# Nixie_3757.net
KiCad netlist of a schematic drawn in EAGLE
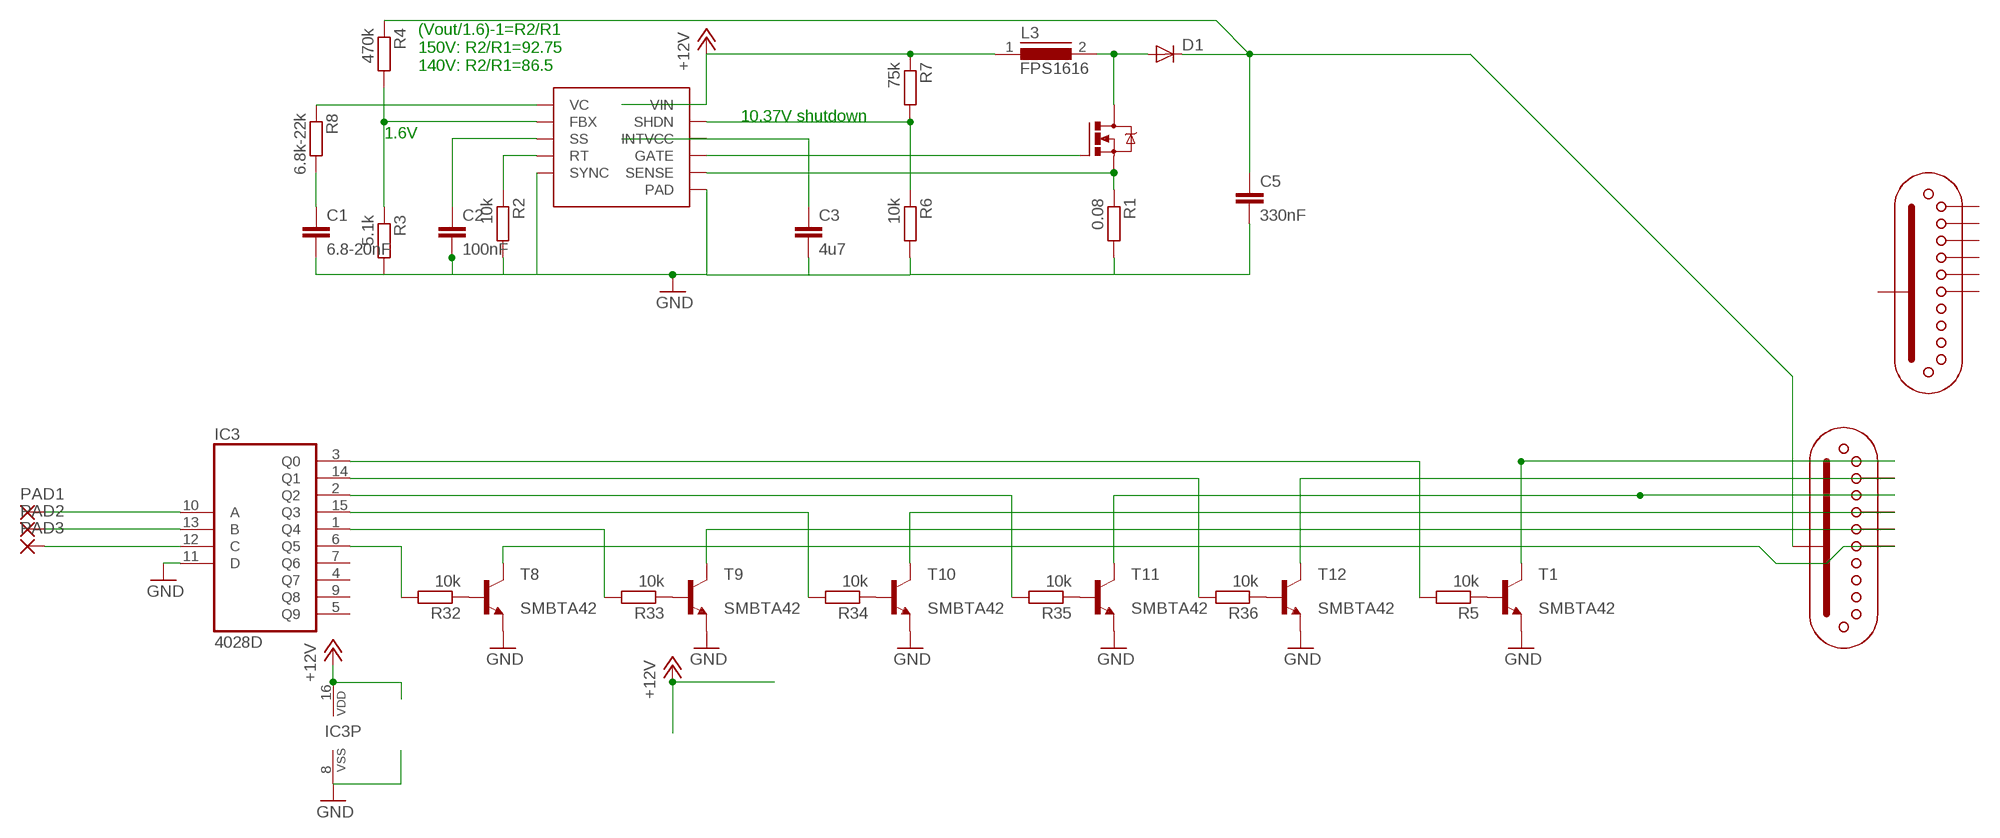
[diagram p0: schematic, sheet 1]

(export (version "E")
  (design (tool "Eeschema 10.0.6"))
  (components
    (comp (ref "C1")
      (value "6.8-20nF")
      (footprint "eagle-import:C0805K")
      (libsource (lib "eagle-import") (part "C-EUC0805K"))
    )
    (comp (ref "C2")
      (value "100nF")
      (footprint "eagle-import:C0805K")
      (libsource (lib "eagle-import") (part "C-EUC0805K"))
    )
    (comp (ref "C3")
      (value "4u7")
      (footprint "eagle-import:C0805K")
      (libsource (lib "eagle-import") (part "C-EUC0805K"))
    )
    (comp (ref "C5")
      (value "330nF")
      (footprint "eagle-import:C1812")
      (libsource (lib "eagle-import") (part "C-EUC1812"))
    )
    (comp (ref "D1")
      (value "DIODE-DO219AB")
      (footprint "eagle-import:DO219AB")
      (libsource (lib "eagle-import") (part "DIODE-DO219AB"))
    )
    (comp (ref "IC3")
      (value "4028D")
      (footprint "eagle-import:SO16")
      (libsource (lib "eagle-import") (part "4028D"))
    )
    (comp (ref "L3")
      (value "FPS1616")
      (footprint "eagle-import:1616FPS_22UH")
      (libsource (lib "eagle-import") (part "FPS1616"))
    )
    (comp (ref "PAD1")
      (value "1,6/0,8")
      (footprint "eagle-import:1,6_0,8")
      (libsource (lib "eagle-import") (part "1,6/0,8"))
    )
    (comp (ref "PAD2")
      (value "1,6/0,8")
      (footprint "eagle-import:1,6_0,8")
      (libsource (lib "eagle-import") (part "1,6/0,8"))
    )
    (comp (ref "PAD3")
      (value "1,6/0,8")
      (footprint "eagle-import:1,6_0,8")
      (libsource (lib "eagle-import") (part "1,6/0,8"))
    )
    (comp (ref "Q4")
      (value "N-MOSFET-TO252-DPAK")
      (footprint "eagle-import:TO252")
      (libsource (lib "eagle-import") (part "N-MOSFET-TO252-DPAK"))
    )
    (comp (ref "R1")
      (value "0.08")
      (footprint "eagle-import:R0805")
      (libsource (lib "eagle-import") (part "R-EU_R0805"))
    )
    (comp (ref "R2")
      (value "10k")
      (footprint "eagle-import:R0805")
      (libsource (lib "eagle-import") (part "R-EU_R0805"))
    )
    (comp (ref "R3")
      (value "5.1k")
      (footprint "eagle-import:R0805")
      (libsource (lib "eagle-import") (part "R-EU_R0805"))
    )
    (comp (ref "R4")
      (value "470k")
      (footprint "eagle-import:R0805")
      (libsource (lib "eagle-import") (part "R-EU_R0805"))
    )
    (comp (ref "R5")
      (value "10k")
      (footprint "eagle-import:R0805")
      (libsource (lib "eagle-import") (part "R-EU_R0805"))
    )
    (comp (ref "R6")
      (value "10k")
      (footprint "eagle-import:R0805")
      (libsource (lib "eagle-import") (part "R-EU_R0805"))
    )
    (comp (ref "R7")
      (value "75k")
      (footprint "eagle-import:R0805")
      (libsource (lib "eagle-import") (part "R-EU_R0805"))
    )
    (comp (ref "R8")
      (value "6.8k-22k")
      (footprint "eagle-import:R0805")
      (libsource (lib "eagle-import") (part "R-EU_R0805"))
    )
    (comp (ref "R32")
      (value "10k")
      (footprint "eagle-import:R0805")
      (libsource (lib "eagle-import") (part "R-EU_R0805"))
    )
    (comp (ref "R33")
      (value "10k")
      (footprint "eagle-import:R0805")
      (libsource (lib "eagle-import") (part "R-EU_R0805"))
    )
    (comp (ref "R34")
      (value "10k")
      (footprint "eagle-import:R0805")
      (libsource (lib "eagle-import") (part "R-EU_R0805"))
    )
    (comp (ref "R35")
      (value "10k")
      (footprint "eagle-import:R0805")
      (libsource (lib "eagle-import") (part "R-EU_R0805"))
    )
    (comp (ref "R36")
      (value "10k")
      (footprint "eagle-import:R0805")
      (libsource (lib "eagle-import") (part "R-EU_R0805"))
    )
    (comp (ref "T1")
      (value "MMBTA42LT1-NPN-SOT23-BEC")
      (footprint "eagle-import:SOT23-BEC")
      (fields (field (name "T") "SMBTA42"))
      (libsource (lib "eagle-import") (part "-NPN-SOT23-BECMMBTA42LT1"))
    )
    (comp (ref "T8")
      (value "MMBTA42LT1-NPN-SOT23-BEC")
      (footprint "eagle-import:SOT23-BEC")
      (fields (field (name "T") "SMBTA42"))
      (libsource (lib "eagle-import") (part "-NPN-SOT23-BECMMBTA42LT1"))
    )
    (comp (ref "T9")
      (value "MMBTA42LT1-NPN-SOT23-BEC")
      (footprint "eagle-import:SOT23-BEC")
      (fields (field (name "T") "SMBTA42"))
      (libsource (lib "eagle-import") (part "-NPN-SOT23-BECMMBTA42LT1"))
    )
    (comp (ref "T10")
      (value "MMBTA42LT1-NPN-SOT23-BEC")
      (footprint "eagle-import:SOT23-BEC")
      (fields (field (name "T") "SMBTA42"))
      (libsource (lib "eagle-import") (part "-NPN-SOT23-BECMMBTA42LT1"))
    )
    (comp (ref "T11")
      (value "MMBTA42LT1-NPN-SOT23-BEC")
      (footprint "eagle-import:SOT23-BEC")
      (fields (field (name "T") "SMBTA42"))
      (libsource (lib "eagle-import") (part "-NPN-SOT23-BECMMBTA42LT1"))
    )
    (comp (ref "T12")
      (value "MMBTA42LT1-NPN-SOT23-BEC")
      (footprint "eagle-import:SOT23-BEC")
      (fields (field (name "T") "SMBTA42"))
      (libsource (lib "eagle-import") (part "-NPN-SOT23-BECMMBTA42LT1"))
    )
    (comp (ref "U$1")
      (value "ZM1020")
      (footprint "eagle-import:ZM1020")
      (libsource (lib "eagle-import") (part "ZM1020"))
    )
    (comp (ref "U$3")
      (value "ZM1020")
      (footprint "eagle-import:ZM1020")
      (libsource (lib "eagle-import") (part "ZM1020"))
    )
    (comp (ref "U1")
      (value "LT3757MSOP-10")
      (footprint "eagle-import:MSOP-10")
      (libsource (lib "eagle-import") (part "LT3757MSOP-10"))
    )
  )
  (nets
    (net (code "1") (name "+12V") (class "Default")
      (node (ref "IC3") (pin "16") (pinfunction "VDD_16") (pintype "power_in"))
      (node (ref "L3") (pin "1") (pinfunction "1_1") (pintype "passive"))
      (node (ref "R7") (pin "1") (pinfunction "1_1") (pintype "passive"))
      (node (ref "U1") (pin "10") (pinfunction "VIN_10") (pintype "bidirectional"))
    )
    (net (code "2") (name "GND") (class "Default")
      (node (ref "C1") (pin "2") (pinfunction "2_2") (pintype "passive"))
      (node (ref "C2") (pin "2") (pinfunction "2_2") (pintype "passive"))
      (node (ref "C3") (pin "2") (pinfunction "2_2") (pintype "passive"))
      (node (ref "C5") (pin "2") (pinfunction "2_2") (pintype "passive"))
      (node (ref "IC3") (pin "11") (pinfunction "D_11") (pintype "input"))
      (node (ref "IC3") (pin "8") (pinfunction "VSS_8") (pintype "power_in"))
      (node (ref "R1") (pin "2") (pinfunction "2_2") (pintype "passive"))
      (node (ref "R2") (pin "2") (pinfunction "2_2") (pintype "passive"))
      (node (ref "R3") (pin "2") (pinfunction "2_2") (pintype "passive"))
      (node (ref "R6") (pin "2") (pinfunction "2_2") (pintype "passive"))
      (node (ref "T1") (pin "E") (pinfunction "E_E") (pintype "passive"))
      (node (ref "T10") (pin "E") (pinfunction "E_E") (pintype "passive"))
      (node (ref "T11") (pin "E") (pinfunction "E_E") (pintype "passive"))
      (node (ref "T12") (pin "E") (pinfunction "E_E") (pintype "passive"))
      (node (ref "T8") (pin "E") (pinfunction "E_E") (pintype "passive"))
      (node (ref "T9") (pin "E") (pinfunction "E_E") (pintype "passive"))
      (node (ref "U1") (pin "5") (pinfunction "SYNC_5") (pintype "bidirectional"))
      (node (ref "U1") (pin "PAD") (pinfunction "PAD_PAD") (pintype "bidirectional"))
    )
    (net (code "3") (name "Net-(C1-Pad1)") (class "Default")
      (node (ref "C1") (pin "1") (pinfunction "1_1") (pintype "passive"))
      (node (ref "R8") (pin "2") (pinfunction "2_2") (pintype "passive"))
    )
    (net (code "4") (name "Net-(IC3A-A)") (class "Default")
      (node (ref "IC3") (pin "10") (pinfunction "A_10") (pintype "input"))
      (node (ref "PAD1") (pin "1") (pinfunction "P_1") (pintype "passive"))
    )
    (net (code "5") (name "Net-(IC3A-B)") (class "Default")
      (node (ref "IC3") (pin "13") (pinfunction "B_13") (pintype "input"))
      (node (ref "PAD2") (pin "1") (pinfunction "P_1") (pintype "passive"))
    )
    (net (code "6") (name "Net-(IC3A-C)") (class "Default")
      (node (ref "IC3") (pin "12") (pinfunction "C_12") (pintype "input"))
      (node (ref "PAD3") (pin "1") (pinfunction "P_1") (pintype "passive"))
    )
    (net (code "7") (name "Net-(IC3A-Q0)") (class "Default")
      (node (ref "IC3") (pin "3") (pinfunction "Q0_3") (pintype "output"))
      (node (ref "R5") (pin "2") (pinfunction "2_2") (pintype "passive"))
    )
    (net (code "8") (name "Net-(IC3A-Q1)") (class "Default")
      (node (ref "IC3") (pin "14") (pinfunction "Q1_14") (pintype "output"))
      (node (ref "R36") (pin "2") (pinfunction "2_2") (pintype "passive"))
    )
    (net (code "9") (name "Net-(IC3A-Q2)") (class "Default")
      (node (ref "IC3") (pin "2") (pinfunction "Q2_2") (pintype "output"))
      (node (ref "R35") (pin "2") (pinfunction "2_2") (pintype "passive"))
    )
    (net (code "10") (name "Net-(IC3A-Q3)") (class "Default")
      (node (ref "IC3") (pin "15") (pinfunction "Q3_15") (pintype "output"))
      (node (ref "R34") (pin "2") (pinfunction "2_2") (pintype "passive"))
    )
    (net (code "11") (name "Net-(IC3A-Q4)") (class "Default")
      (node (ref "IC3") (pin "1") (pinfunction "Q4_1") (pintype "output"))
      (node (ref "R33") (pin "2") (pinfunction "2_2") (pintype "passive"))
    )
    (net (code "12") (name "Net-(IC3A-Q5)") (class "Default")
      (node (ref "IC3") (pin "6") (pinfunction "Q5_6") (pintype "output"))
      (node (ref "R32") (pin "2") (pinfunction "2_2") (pintype "passive"))
    )
    (net (code "13") (name "Net-(Q4-D)") (class "Default")
      (node (ref "D1") (pin "A") (pinfunction "A_A") (pintype "passive"))
      (node (ref "L3") (pin "2") (pinfunction "2_2") (pintype "passive"))
      (node (ref "Q4") (pin "2") (pinfunction "D_2") (pintype "passive"))
    )
    (net (code "14") (name "Net-(Q4-G)") (class "Default")
      (node (ref "Q4") (pin "1") (pinfunction "G_1") (pintype "passive"))
      (node (ref "U1") (pin "7") (pinfunction "GATE_7") (pintype "bidirectional"))
    )
    (net (code "15") (name "Net-(Q4-S)") (class "Default")
      (node (ref "Q4") (pin "3") (pinfunction "S_3") (pintype "passive"))
      (node (ref "R1") (pin "1") (pinfunction "1_1") (pintype "passive"))
      (node (ref "U1") (pin "6") (pinfunction "SENSE_6") (pintype "bidirectional"))
    )
    (net (code "16") (name "Net-(R5-Pad1)") (class "Default")
      (node (ref "R5") (pin "1") (pinfunction "1_1") (pintype "passive"))
      (node (ref "T1") (pin "B") (pinfunction "B_B") (pintype "passive"))
    )
    (net (code "17") (name "Net-(R32-Pad1)") (class "Default")
      (node (ref "R32") (pin "1") (pinfunction "1_1") (pintype "passive"))
      (node (ref "T8") (pin "B") (pinfunction "B_B") (pintype "passive"))
    )
    (net (code "18") (name "Net-(R33-Pad1)") (class "Default")
      (node (ref "R33") (pin "1") (pinfunction "1_1") (pintype "passive"))
      (node (ref "T9") (pin "B") (pinfunction "B_B") (pintype "passive"))
    )
    (net (code "19") (name "Net-(R34-Pad1)") (class "Default")
      (node (ref "R34") (pin "1") (pinfunction "1_1") (pintype "passive"))
      (node (ref "T10") (pin "B") (pinfunction "B_B") (pintype "passive"))
    )
    (net (code "20") (name "Net-(R35-Pad1)") (class "Default")
      (node (ref "R35") (pin "1") (pinfunction "1_1") (pintype "passive"))
      (node (ref "T11") (pin "B") (pinfunction "B_B") (pintype "passive"))
    )
    (net (code "21") (name "Net-(R36-Pad1)") (class "Default")
      (node (ref "R36") (pin "1") (pinfunction "1_1") (pintype "passive"))
      (node (ref "T12") (pin "B") (pinfunction "B_B") (pintype "passive"))
    )
    (net (code "22") (name "Net-(T8-PadC)") (class "Default")
      (node (ref "T8") (pin "C") (pinfunction "C_C") (pintype "passive"))
      (node (ref "U$1") (pin "5") (pinfunction "5_5") (pintype "bidirectional"))
    )
    (net (code "23") (name "Net-(T9-PadC)") (class "Default")
      (node (ref "T9") (pin "C") (pinfunction "C_C") (pintype "passive"))
      (node (ref "U$1") (pin "4") (pinfunction "4_4") (pintype "bidirectional"))
    )
    (net (code "24") (name "Net-(T10-PadC)") (class "Default")
      (node (ref "T10") (pin "C") (pinfunction "C_C") (pintype "passive"))
      (node (ref "U$1") (pin "3") (pinfunction "3_3") (pintype "bidirectional"))
    )
    (net (code "25") (name "Net-(T11-PadC)") (class "Default")
      (node (ref "T11") (pin "C") (pinfunction "C_C") (pintype "passive"))
      (node (ref "U$1") (pin "2") (pinfunction "2_2") (pintype "bidirectional"))
    )
    (net (code "26") (name "Net-(T12-PadC)") (class "Default")
      (node (ref "T12") (pin "C") (pinfunction "C_C") (pintype "passive"))
      (node (ref "U$1") (pin "1") (pinfunction "1_1") (pintype "bidirectional"))
    )
    (net (code "27") (name "Net-(U$1-0)") (class "Default")
      (node (ref "T1") (pin "C") (pinfunction "C_C") (pintype "passive"))
      (node (ref "U$1") (pin "11") (pinfunction "0_11") (pintype "bidirectional"))
    )
    (net (code "28") (name "Net-(U$1-A)") (class "Default")
      (node (ref "C5") (pin "1") (pinfunction "1_1") (pintype "passive"))
      (node (ref "D1") (pin "C") (pinfunction "C_C") (pintype "passive"))
      (node (ref "R4") (pin "1") (pinfunction "1_1") (pintype "passive"))
      (node (ref "U$1") (pin "12") (pinfunction "A_12") (pintype "bidirectional"))
    )
    (net (code "29") (name "Net-(U1-FBX)") (class "Default")
      (node (ref "R3") (pin "1") (pinfunction "1_1") (pintype "passive"))
      (node (ref "R4") (pin "2") (pinfunction "2_2") (pintype "passive"))
      (node (ref "U1") (pin "2") (pinfunction "FBX_2") (pintype "bidirectional"))
    )
    (net (code "30") (name "Net-(U1-INTVCC)") (class "Default")
      (node (ref "C3") (pin "1") (pinfunction "1_1") (pintype "passive"))
      (node (ref "U1") (pin "8") (pinfunction "INTVCC_8") (pintype "bidirectional"))
    )
    (net (code "31") (name "Net-(U1-RT)") (class "Default")
      (node (ref "R2") (pin "1") (pinfunction "1_1") (pintype "passive"))
      (node (ref "U1") (pin "4") (pinfunction "RT_4") (pintype "bidirectional"))
    )
    (net (code "32") (name "Net-(U1-SHDN)") (class "Default")
      (node (ref "R6") (pin "1") (pinfunction "1_1") (pintype "passive"))
      (node (ref "R7") (pin "2") (pinfunction "2_2") (pintype "passive"))
      (node (ref "U1") (pin "9") (pinfunction "SHDN_9") (pintype "bidirectional"))
    )
    (net (code "33") (name "Net-(U1-SS)") (class "Default")
      (node (ref "C2") (pin "1") (pinfunction "1_1") (pintype "passive"))
      (node (ref "U1") (pin "3") (pinfunction "SS_3") (pintype "bidirectional"))
    )
    (net (code "34") (name "Net-(U1-VC)") (class "Default")
      (node (ref "R8") (pin "1") (pinfunction "1_1") (pintype "passive"))
      (node (ref "U1") (pin "1") (pinfunction "VC_1") (pintype "bidirectional"))
    )
    (net (code "35") (name "unconnected-(IC3A-Q6-Pad7)") (class "Default")
      (node (ref "IC3") (pin "7") (pinfunction "Q6_7") (pintype "output"))
    )
    (net (code "36") (name "unconnected-(IC3A-Q7-Pad4)") (class "Default")
      (node (ref "IC3") (pin "4") (pinfunction "Q7_4") (pintype "output"))
    )
    (net (code "37") (name "unconnected-(IC3A-Q8-Pad9)") (class "Default")
      (node (ref "IC3") (pin "9") (pinfunction "Q8_9") (pintype "output"))
    )
    (net (code "38") (name "unconnected-(IC3A-Q9-Pad5)") (class "Default")
      (node (ref "IC3") (pin "5") (pinfunction "Q9_5") (pintype "output"))
    )
    (net (code "39") (name "unconnected-(U$3-0-Pad11)") (class "Default")
      (node (ref "U$3") (pin "11") (pinfunction "0_11") (pintype "bidirectional"))
    )
    (net (code "40") (name "unconnected-(U$3-A-Pad12)") (class "Default")
      (node (ref "U$3") (pin "12") (pinfunction "A_12") (pintype "bidirectional"))
    )
    (net (code "41") (name "unconnected-(U$3-Pad1)") (class "Default")
      (node (ref "U$3") (pin "1") (pinfunction "1_1") (pintype "bidirectional"))
    )
    (net (code "42") (name "unconnected-(U$3-Pad2)") (class "Default")
      (node (ref "U$3") (pin "2") (pinfunction "2_2") (pintype "bidirectional"))
    )
    (net (code "43") (name "unconnected-(U$3-Pad3)") (class "Default")
      (node (ref "U$3") (pin "3") (pinfunction "3_3") (pintype "bidirectional"))
    )
    (net (code "44") (name "unconnected-(U$3-Pad4)") (class "Default")
      (node (ref "U$3") (pin "4") (pinfunction "4_4") (pintype "bidirectional"))
    )
    (net (code "45") (name "unconnected-(U$3-Pad5)") (class "Default")
      (node (ref "U$3") (pin "5") (pinfunction "5_5") (pintype "bidirectional"))
    )
  )
)
